# Charging.net
KiCad netlist of a schematic drawn in Altium Designer
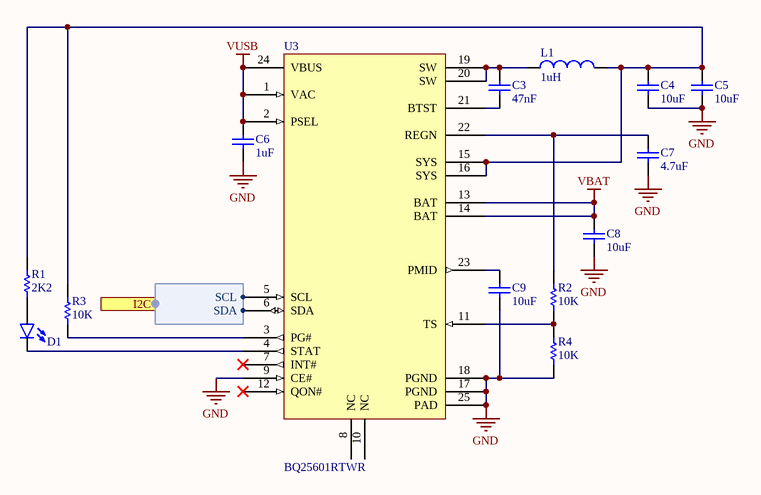
[diagram p0: Charging.SchDoc]

(export (version "E")
  (design (tool "Eeschema 10.0.6"))
  (components
    (comp (ref "C3")
      (value "47nF")
      (footprint "C0402[1005X55]")
      (description "47nF 16V 10% 0402 (1005 Metric)")
      (fields (field (name "PARTNUMBER") "GCM155R71C473KA37D") (field (name "MANUFACTURER") "Murata"))
      (libsource (lib "Capacitors") (part "CAP_47nF_16V_0402_10%"))
    )
    (comp (ref "C4")
      (value "10uF")
      (footprint "C0402[1005X55]")
      (description "10uF 6.3V 20% 0402 (1005 Metric)")
      (fields (field (name "PARTNUMBER") "GRM155R60J106ME44D") (field (name "MANUFACTURER") "Murata"))
      (libsource (lib "Capacitors") (part "CAP_10uF_6.3V_0402_20%"))
    )
    (comp (ref "C5")
      (value "10uF")
      (footprint "C0402[1005X55]")
      (description "10uF 6.3V 20% 0402 (1005 Metric)")
      (fields (field (name "PARTNUMBER") "GRM155R60J106ME44D") (field (name "MANUFACTURER") "Murata"))
      (libsource (lib "Capacitors") (part "CAP_10uF_6.3V_0402_20%"))
    )
    (comp (ref "C6")
      (value "1uF")
      (footprint "C0402[1005X55]")
      (description "1uF 16V 10% 0402 (1005 Metric)")
      (fields (field (name "PARTNUMBER") "GRM155R61C105KE01D") (field (name "MANUFACTURER") "Murata"))
      (libsource (lib "Capacitors") (part "CAP_1uF_16V_0402_10%"))
    )
    (comp (ref "C7")
      (value "4.7uF")
      (footprint "C0402[1005X55]")
      (description "4.7uF 10V 10% 0402 (1005 Metric)")
      (fields (field (name "PARTNUMBER") "ZRB15XR61A475KE01D") (field (name "MANUFACTURER") "Murata"))
      (libsource (lib "Capacitors") (part "CAP_4.7uF_10V_0402_10%"))
    )
    (comp (ref "C8")
      (value "10uF")
      (footprint "C0402[1005X55]")
      (description "10uF 6.3V 20% 0402 (1005 Metric)")
      (fields (field (name "PARTNUMBER") "GRM155R60J106ME44D") (field (name "MANUFACTURER") "Murata"))
      (libsource (lib "Capacitors") (part "CAP_10uF_6.3V_0402_20%"))
    )
    (comp (ref "C9")
      (value "10uF")
      (footprint "C0603[1608X92]")
      (description "10uF 35V 10% 0603 (1608 Metric)")
      (fields (field (name "PARTNUMBER") "GRM188R6YA106MA73D") (field (name "MANUFACTURER") "Murata"))
      (libsource (lib "Capacitors") (part "CAP_10uF_35V_0603_10%"))
    )
    (comp (ref "D1")
      (value "LED_0603_GREEN_5mA")
      (footprint "LED0603")
      (fields (field (name "PARTNUMBER") "LTST-C193TGKT-5A") (field (name "MANUFACTURER") "Lite-On Inc."))
      (libsource (lib "LEDs") (part "LED_0603_GREEN_5mA"))
    )
    (comp (ref "L1")
      (value "1uH")
      (footprint "IND1008")
      (description "1uH 20% 4.7A 1008")
      (fields (field (name "PARTNUMBER") "DFE252012F-2R2M=P2") (field (name "MANUFACTURER") "Murata"))
      (libsource (lib "Inductors") (part "IND_1uH_4.7A_1008_20%"))
    )
    (comp (ref "R1")
      (value "2K2")
      (footprint "R0402[1005]")
      (description "2K2 0.063W 1% 0402 (1005 Metric)")
      (fields (field (name "MANUFACTURER") "KOA Speer") (field (name "PARTNUMBER") "RK73H1ETTP2201F"))
      (libsource (lib "Resistors") (part "RES_2K2_0402_1%"))
    )
    (comp (ref "R2")
      (value "10K")
      (footprint "R0402[1005]")
      (description "10K 0.063W 1% 0402 (1005 Metric)")
      (fields (field (name "MANUFACTURER") "KOA Speer") (field (name "PARTNUMBER") "RK73H1ETTP1002F"))
      (libsource (lib "Resistors") (part "RES_10K_0402_1%"))
    )
    (comp (ref "R3")
      (value "10K")
      (footprint "R0402[1005]")
      (description "10K 0.063W 1% 0402 (1005 Metric)")
      (fields (field (name "MANUFACTURER") "KOA Speer") (field (name "PARTNUMBER") "RK73H1ETTP1002F"))
      (libsource (lib "Resistors") (part "RES_10K_0402_1%"))
    )
    (comp (ref "R4")
      (value "10K")
      (footprint "R0402[1005]")
      (description "10K 0.063W 1% 0402 (1005 Metric)")
      (fields (field (name "MANUFACTURER") "KOA Speer") (field (name "PARTNUMBER") "RK73H1ETTP1002F"))
      (libsource (lib "Resistors") (part "RES_10K_0402_1%"))
    )
    (comp (ref "U3")
      (value "BQ25601RTWR")
      (footprint "WQFN-24")
      (fields (field (name "MANUFACTURER") "Texas Instruments"))
      (libsource (lib "ICs") (part "BQ25601RTWR"))
    )
  )
  (nets
    (net (code "2") (name "/SCL") (class "Default")
      (node (ref "U3") (pin "5") (pinfunction "SCL_5") (pintype "input"))
    )
    (net (code "3") (name "/SDA") (class "Default")
      (node (ref "U3") (pin "6") (pinfunction "SDA_6") (pintype "bidirectional"))
    )
    (net (code "5") (name "GND") (class "Default")
      (node (ref "C4") (pin "1") (pinfunction "1_1") (pintype "passive"))
      (node (ref "C5") (pin "1") (pinfunction "1_1") (pintype "passive"))
      (node (ref "C6") (pin "1") (pinfunction "1_1") (pintype "passive"))
      (node (ref "C7") (pin "1") (pinfunction "1_1") (pintype "passive"))
      (node (ref "C8") (pin "1") (pinfunction "1_1") (pintype "passive"))
      (node (ref "C9") (pin "1") (pinfunction "1_1") (pintype "passive"))
      (node (ref "R4") (pin "1") (pinfunction "1_1") (pintype "passive"))
      (node (ref "U3") (pin "17") (pinfunction "PGND_17") (pintype "power_in"))
      (node (ref "U3") (pin "18") (pinfunction "PGND_18") (pintype "power_in"))
      (node (ref "U3") (pin "25") (pinfunction "PAD_25") (pintype "power_in"))
      (node (ref "U3") (pin "9") (pinfunction "CE#_9") (pintype "input"))
    )
    (net (code "6") (name "Net-(C3-Pad2)") (class "Default")
      (node (ref "C3") (pin "2") (pinfunction "2_2") (pintype "passive"))
      (node (ref "L1") (pin "1") (pinfunction "1_1") (pintype "passive"))
      (node (ref "U3") (pin "19") (pinfunction "SW_19") (pintype "power_in"))
      (node (ref "U3") (pin "20") (pinfunction "SW_20") (pintype "power_in"))
    )
    (net (code "7") (name "Net-(C4-Pad2)") (class "Default")
      (node (ref "C4") (pin "2") (pinfunction "2_2") (pintype "passive"))
      (node (ref "C5") (pin "2") (pinfunction "2_2") (pintype "passive"))
      (node (ref "L1") (pin "2") (pinfunction "2_2") (pintype "passive"))
      (node (ref "R1") (pin "2") (pinfunction "2_2") (pintype "passive"))
      (node (ref "R3") (pin "2") (pinfunction "2_2") (pintype "passive"))
      (node (ref "U3") (pin "15") (pinfunction "SYS_15") (pintype "power_in"))
      (node (ref "U3") (pin "16") (pinfunction "SYS_16") (pintype "power_in"))
    )
    (net (code "8") (name "Net-(D1-PadA)") (class "Default")
      (node (ref "D1") (pin "A") (pinfunction "A_A") (pintype "passive"))
      (node (ref "R1") (pin "1") (pinfunction "1_1") (pintype "passive"))
    )
    (net (code "9") (name "Net-(U3-BTST)") (class "Default")
      (node (ref "C3") (pin "1") (pinfunction "1_1") (pintype "passive"))
      (node (ref "U3") (pin "21") (pinfunction "BTST_21") (pintype "power_in"))
    )
    (net (code "10") (name "Net-(U3-PG#)") (class "Default")
      (node (ref "R3") (pin "1") (pinfunction "1_1") (pintype "passive"))
      (node (ref "U3") (pin "3") (pinfunction "PG#_3") (pintype "output"))
    )
    (net (code "11") (name "Net-(U3-PMID)") (class "Default")
      (node (ref "C9") (pin "2") (pinfunction "2_2") (pintype "passive"))
      (node (ref "U3") (pin "23") (pinfunction "PMID_23") (pintype "output"))
    )
    (net (code "12") (name "Net-(U3-REGN)") (class "Default")
      (node (ref "C7") (pin "2") (pinfunction "2_2") (pintype "passive"))
      (node (ref "R2") (pin "2") (pinfunction "2_2") (pintype "passive"))
      (node (ref "U3") (pin "22") (pinfunction "REGN_22") (pintype "power_in"))
    )
    (net (code "13") (name "Net-(U3-STAT)") (class "Default")
      (node (ref "D1") (pin "C") (pinfunction "C_C") (pintype "passive"))
      (node (ref "U3") (pin "4") (pinfunction "STAT_4") (pintype "output"))
    )
    (net (code "14") (name "Net-(U3-TS)") (class "Default")
      (node (ref "R2") (pin "1") (pinfunction "1_1") (pintype "passive"))
      (node (ref "R4") (pin "2") (pinfunction "2_2") (pintype "passive"))
      (node (ref "U3") (pin "11") (pinfunction "TS_11") (pintype "input"))
    )
    (net (code "15") (name "VBAT") (class "Default")
      (node (ref "C8") (pin "2") (pinfunction "2_2") (pintype "passive"))
      (node (ref "U3") (pin "13") (pinfunction "BAT_13") (pintype "power_in"))
      (node (ref "U3") (pin "14") (pinfunction "BAT_14") (pintype "power_in"))
    )
    (net (code "16") (name "VUSB") (class "Default")
      (node (ref "C6") (pin "2") (pinfunction "2_2") (pintype "passive"))
      (node (ref "U3") (pin "1") (pinfunction "VAC_1") (pintype "input"))
      (node (ref "U3") (pin "2") (pinfunction "PSEL_2") (pintype "input"))
      (node (ref "U3") (pin "24") (pinfunction "VBUS_24") (pintype "power_in"))
    )
    (net (code "17") (name "unconnected-(U3-INT#-Pad7)") (class "Default")
      (node (ref "U3") (pin "7") (pinfunction "INT#_7") (pintype "output+no_connect"))
    )
    (net (code "18") (name "unconnected-(U3-NC-Pad8)") (class "Default")
      (node (ref "U3") (pin "8") (pinfunction "NC_8") (pintype "passive"))
    )
    (net (code "19") (name "unconnected-(U3-NC-Pad10)") (class "Default")
      (node (ref "U3") (pin "10") (pinfunction "NC_10") (pintype "passive"))
    )
    (net (code "20") (name "unconnected-(U3-QON#-Pad12)") (class "Default")
      (node (ref "U3") (pin "12") (pinfunction "QON#_12") (pintype "input+no_connect"))
    )
  )
)
